# spice-usbm.net
KiCad netlist of a schematic drawn in EAGLE
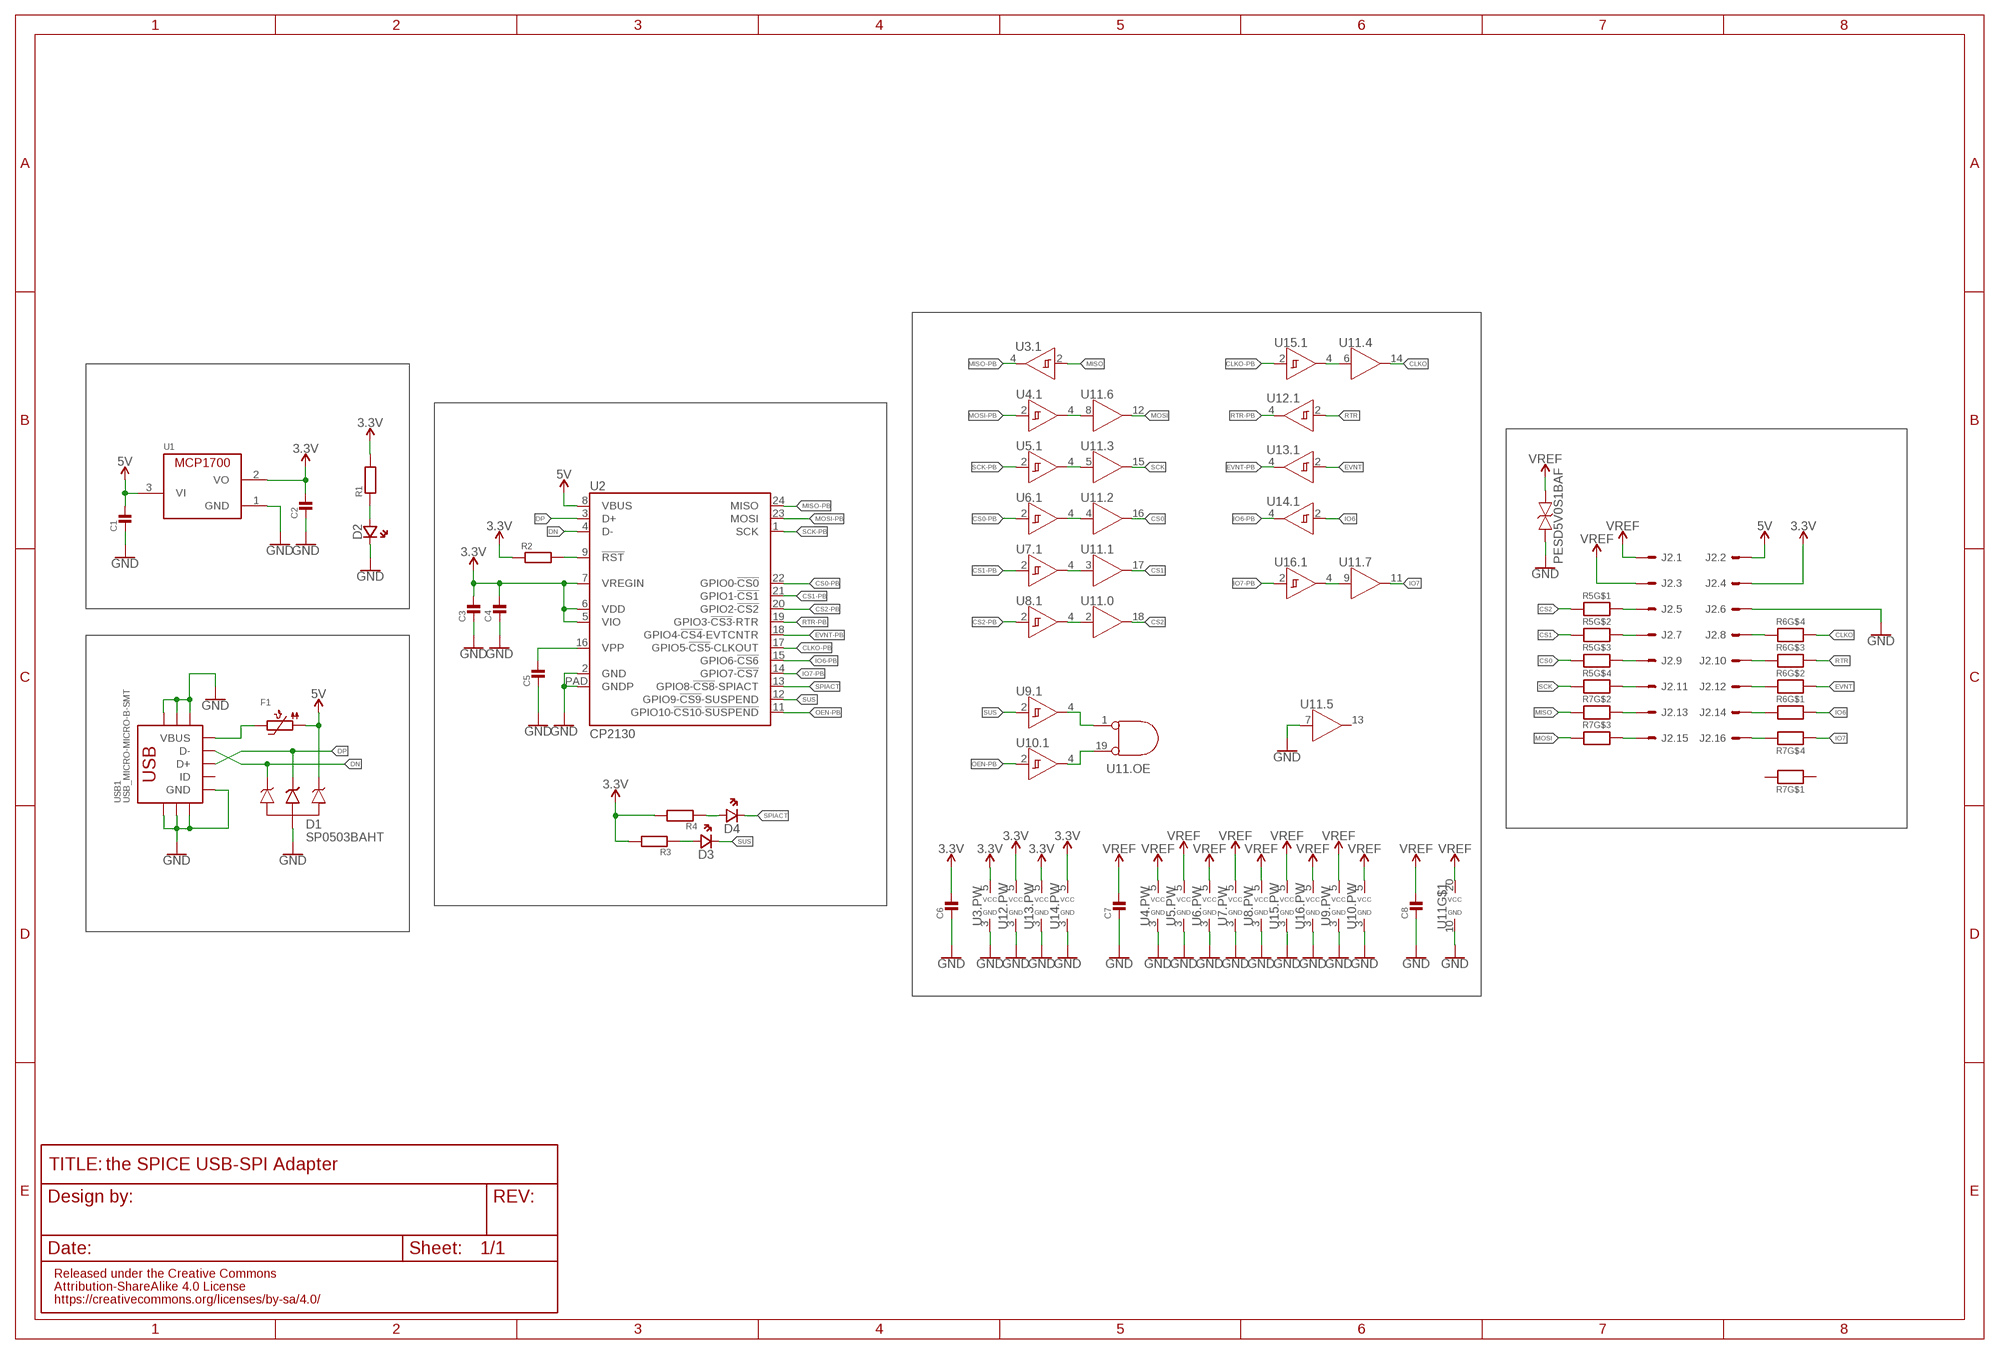
[diagram p0: schematic, sheet 1]

(export (version "E")
  (design (tool "Eeschema 10.0.6"))
  (components
    (comp (ref "C1")
      (value "MLCC0603")
      (footprint "eagle-import:0603_WAVE")
      (libsource (lib "eagle-import") (part "MLCC0603"))
    )
    (comp (ref "C2")
      (value "MLCC0603")
      (footprint "eagle-import:0603_WAVE")
      (libsource (lib "eagle-import") (part "MLCC0603"))
    )
    (comp (ref "C3")
      (value "MLCC0603")
      (footprint "eagle-import:0603_WAVE")
      (libsource (lib "eagle-import") (part "MLCC0603"))
    )
    (comp (ref "C4")
      (value "MLCC0603")
      (footprint "eagle-import:0603_WAVE")
      (libsource (lib "eagle-import") (part "MLCC0603"))
    )
    (comp (ref "C5")
      (value "MLCC0603")
      (footprint "eagle-import:0603_WAVE")
      (libsource (lib "eagle-import") (part "MLCC0603"))
    )
    (comp (ref "C6")
      (value "MLCC0603")
      (footprint "eagle-import:0603_WAVE")
      (libsource (lib "eagle-import") (part "MLCC0603"))
    )
    (comp (ref "C7")
      (value "MLCC0603")
      (footprint "eagle-import:0603_WAVE")
      (libsource (lib "eagle-import") (part "MLCC0603"))
    )
    (comp (ref "C8")
      (value "MLCC0603")
      (footprint "eagle-import:0603_WAVE")
      (libsource (lib "eagle-import") (part "MLCC0603"))
    )
    (comp (ref "D1")
      (value "SP0503BAHT")
      (footprint "eagle-import:SOT143")
      (libsource (lib "eagle-import") (part "SP0503BAHT"))
    )
    (comp (ref "D2")
      (value "LED0603")
      (footprint "eagle-import:CHIPLED_0603")
      (libsource (lib "eagle-import") (part "LED0603"))
    )
    (comp (ref "D3")
      (value "LED0603")
      (footprint "eagle-import:CHIPLED_0603")
      (libsource (lib "eagle-import") (part "LED0603"))
    )
    (comp (ref "D4")
      (value "LED0603")
      (footprint "eagle-import:CHIPLED_0603")
      (libsource (lib "eagle-import") (part "LED0603"))
    )
    (comp (ref "D5")
      (value "PESD5V0S1BAF")
      (footprint "eagle-import:SOD323")
      (libsource (lib "eagle-import") (part "PESD5V0S1BAF"))
    )
    (comp (ref "F1")
      (value "PTC1210")
      (footprint "eagle-import:PTC1210")
      (libsource (lib "eagle-import") (part "PTC1210"))
    )
    (comp (ref "J2")
      (value "2X8")
      (footprint "eagle-import:2X8_2.54")
      (libsource (lib "eagle-import") (part "2X8"))
    )
    (comp (ref "R1")
      (value "RESISTOR0603")
      (footprint "eagle-import:0603_WAVE")
      (libsource (lib "eagle-import") (part "RESISTOR0603"))
    )
    (comp (ref "R2")
      (value "RESISTOR0603")
      (footprint "eagle-import:0603_WAVE")
      (libsource (lib "eagle-import") (part "RESISTOR0603"))
    )
    (comp (ref "R3")
      (value "RESISTOR0603")
      (footprint "eagle-import:0603_WAVE")
      (libsource (lib "eagle-import") (part "RESISTOR0603"))
    )
    (comp (ref "R4")
      (value "RESISTOR0603")
      (footprint "eagle-import:0603_WAVE")
      (libsource (lib "eagle-import") (part "RESISTOR0603"))
    )
    (comp (ref "R5")
      (value "RESISTOR_4PACK")
      (footprint "eagle-import:RESPACK_4X0603")
      (libsource (lib "eagle-import") (part "RESISTOR_4PACK"))
    )
    (comp (ref "R6")
      (value "RESISTOR_4PACK")
      (footprint "eagle-import:RESPACK_4X0603")
      (libsource (lib "eagle-import") (part "RESISTOR_4PACK"))
    )
    (comp (ref "R7")
      (value "RESISTOR_4PACK")
      (footprint "eagle-import:RESPACK_4X0603")
      (libsource (lib "eagle-import") (part "RESISTOR_4PACK"))
    )
    (comp (ref "U1")
      (value "MCP1700T-3302TT")
      (footprint "eagle-import:SOT-23")
      (libsource (lib "eagle-import") (part "MCP1700T-3302TT"))
    )
    (comp (ref "U2")
      (value "CP2130")
      (footprint "eagle-import:QFN24")
      (libsource (lib "eagle-import") (part "CP2130"))
    )
    (comp (ref "U3")
      (value "74LVC1G17")
      (footprint "eagle-import:SC70-5")
      (libsource (lib "eagle-import") (part "74LVC1G17"))
    )
    (comp (ref "U4")
      (value "74LVC1G17")
      (footprint "eagle-import:SC70-5")
      (libsource (lib "eagle-import") (part "74LVC1G17"))
    )
    (comp (ref "U5")
      (value "74LVC1G17")
      (footprint "eagle-import:SC70-5")
      (libsource (lib "eagle-import") (part "74LVC1G17"))
    )
    (comp (ref "U6")
      (value "74LVC1G17")
      (footprint "eagle-import:SC70-5")
      (libsource (lib "eagle-import") (part "74LVC1G17"))
    )
    (comp (ref "U7")
      (value "74LVC1G17")
      (footprint "eagle-import:SC70-5")
      (libsource (lib "eagle-import") (part "74LVC1G17"))
    )
    (comp (ref "U8")
      (value "74LVC1G17")
      (footprint "eagle-import:SC70-5")
      (libsource (lib "eagle-import") (part "74LVC1G17"))
    )
    (comp (ref "U9")
      (value "74LVC1G17")
      (footprint "eagle-import:SC70-5")
      (libsource (lib "eagle-import") (part "74LVC1G17"))
    )
    (comp (ref "U10")
      (value "74LVC1G17")
      (footprint "eagle-import:SC70-5")
      (libsource (lib "eagle-import") (part "74LVC1G17"))
    )
    (comp (ref "U11")
      (value "74HC541")
      (footprint "eagle-import:TSSOP20")
      (libsource (lib "eagle-import") (part "74HC541"))
    )
    (comp (ref "U12")
      (value "74LVC1G17")
      (footprint "eagle-import:SC70-5")
      (libsource (lib "eagle-import") (part "74LVC1G17"))
    )
    (comp (ref "U13")
      (value "74LVC1G17")
      (footprint "eagle-import:SC70-5")
      (libsource (lib "eagle-import") (part "74LVC1G17"))
    )
    (comp (ref "U14")
      (value "74LVC1G17")
      (footprint "eagle-import:SC70-5")
      (libsource (lib "eagle-import") (part "74LVC1G17"))
    )
    (comp (ref "U15")
      (value "74LVC1G17")
      (footprint "eagle-import:SC70-5")
      (libsource (lib "eagle-import") (part "74LVC1G17"))
    )
    (comp (ref "U16")
      (value "74LVC1G17")
      (footprint "eagle-import:SC70-5")
      (libsource (lib "eagle-import") (part "74LVC1G17"))
    )
    (comp (ref "USB1")
      (value "USB_MICRO-MICRO-B-SMT")
      (footprint "eagle-import:USB-MICRO-SMD")
      (libsource (lib "eagle-import") (part "USB_MICRO-MICRO-B-SMT"))
    )
  )
  (nets
    (net (code "1") (name "3.3V") (class "Default")
      (node (ref "C2") (pin "P$1") (pinfunction "P$1_P$1") (pintype "bidirectional"))
      (node (ref "C3") (pin "P$1") (pinfunction "P$1_P$1") (pintype "bidirectional"))
      (node (ref "C4") (pin "P$1") (pinfunction "P$1_P$1") (pintype "bidirectional"))
      (node (ref "C6") (pin "P$1") (pinfunction "P$1_P$1") (pintype "bidirectional"))
      (node (ref "J2") (pin "4") (pinfunction "S_4") (pintype "passive"))
      (node (ref "R1") (pin "P$2") (pinfunction "P$2_P$2") (pintype "bidirectional"))
      (node (ref "R2") (pin "P$1") (pinfunction "P$1_P$1") (pintype "bidirectional"))
      (node (ref "R3") (pin "P$2") (pinfunction "P$2_P$2") (pintype "bidirectional"))
      (node (ref "R4") (pin "P$2") (pinfunction "P$2_P$2") (pintype "bidirectional"))
      (node (ref "U1") (pin "2") (pinfunction "VO_2") (pintype "bidirectional"))
      (node (ref "U12") (pin "5") (pinfunction "VCC_5") (pintype "bidirectional"))
      (node (ref "U13") (pin "5") (pinfunction "VCC_5") (pintype "bidirectional"))
      (node (ref "U14") (pin "5") (pinfunction "VCC_5") (pintype "bidirectional"))
      (node (ref "U2") (pin "5") (pinfunction "VIO_5") (pintype "bidirectional"))
      (node (ref "U2") (pin "6") (pinfunction "VDD_6") (pintype "bidirectional"))
      (node (ref "U2") (pin "7") (pinfunction "VREGIN_7") (pintype "bidirectional"))
      (node (ref "U3") (pin "5") (pinfunction "VCC_5") (pintype "bidirectional"))
    )
    (net (code "2") (name "5V") (class "Default")
      (node (ref "C1") (pin "P$1") (pinfunction "P$1_P$1") (pintype "bidirectional"))
      (node (ref "D1") (pin "4") (pinfunction "4_4") (pintype "bidirectional"))
      (node (ref "F1") (pin "P$1") (pinfunction "1_P$1") (pintype "passive"))
      (node (ref "J2") (pin "2") (pinfunction "S_2") (pintype "passive"))
      (node (ref "U1") (pin "3") (pinfunction "VI_3") (pintype "bidirectional"))
      (node (ref "U2") (pin "8") (pinfunction "VBUS_8") (pintype "bidirectional"))
    )
    (net (code "3") (name "CLKO") (class "Default")
      (node (ref "R6") (pin "5") (pinfunction "2_5") (pintype "passive"))
      (node (ref "U11") (pin "14") (pinfunction "Y_14") (pintype "output"))
    )
    (net (code "4") (name "CLKO-PB") (class "Default")
      (node (ref "U15") (pin "2") (pinfunction "A_2") (pintype "input"))
      (node (ref "U2") (pin "17") (pinfunction "GPIO5-~{CS5}-CLKOUT_17") (pintype "bidirectional"))
    )
    (net (code "5") (name "CS0") (class "Default")
      (node (ref "R5") (pin "3") (pinfunction "1_3") (pintype "passive"))
      (node (ref "U11") (pin "16") (pinfunction "Y_16") (pintype "output"))
    )
    (net (code "6") (name "CS0-PB") (class "Default")
      (node (ref "U2") (pin "22") (pinfunction "GPIO0-~{CS0}_22") (pintype "bidirectional"))
      (node (ref "U6") (pin "2") (pinfunction "A_2") (pintype "input"))
    )
    (net (code "7") (name "CS1") (class "Default")
      (node (ref "R5") (pin "2") (pinfunction "1_2") (pintype "passive"))
      (node (ref "U11") (pin "17") (pinfunction "Y_17") (pintype "output"))
    )
    (net (code "8") (name "CS1-PB") (class "Default")
      (node (ref "U2") (pin "21") (pinfunction "GPIO1-~{CS1}_21") (pintype "bidirectional"))
      (node (ref "U7") (pin "2") (pinfunction "A_2") (pintype "input"))
    )
    (net (code "9") (name "CS2") (class "Default")
      (node (ref "R5") (pin "1") (pinfunction "1_1") (pintype "passive"))
      (node (ref "U11") (pin "18") (pinfunction "Y_18") (pintype "output"))
    )
    (net (code "10") (name "CS2-PB") (class "Default")
      (node (ref "U2") (pin "20") (pinfunction "GPIO2-~{CS2}_20") (pintype "bidirectional"))
      (node (ref "U8") (pin "2") (pinfunction "A_2") (pintype "input"))
    )
    (net (code "11") (name "DN") (class "Default")
      (node (ref "D1") (pin "2") (pinfunction "2_2") (pintype "bidirectional"))
      (node (ref "U2") (pin "4") (pinfunction "D-_4") (pintype "bidirectional"))
      (node (ref "USB1") (pin "D-") (pinfunction "D-_D-") (pintype "bidirectional"))
    )
    (net (code "12") (name "DP") (class "Default")
      (node (ref "D1") (pin "3") (pinfunction "3_3") (pintype "bidirectional"))
      (node (ref "U2") (pin "3") (pinfunction "D+_3") (pintype "bidirectional"))
      (node (ref "USB1") (pin "D+") (pinfunction "D+_D+") (pintype "bidirectional"))
    )
    (net (code "13") (name "EVNT") (class "Default")
      (node (ref "R6") (pin "7") (pinfunction "2_7") (pintype "passive"))
      (node (ref "U13") (pin "2") (pinfunction "A_2") (pintype "input"))
    )
    (net (code "14") (name "EVNT-PB") (class "Default")
      (node (ref "U13") (pin "4") (pinfunction "Y_4") (pintype "output"))
      (node (ref "U2") (pin "18") (pinfunction "GPIO4-~{CS4}-EVTCNTR_18") (pintype "bidirectional"))
    )
    (net (code "15") (name "GND") (class "Default")
      (node (ref "C1") (pin "P$2") (pinfunction "P$2_P$2") (pintype "bidirectional"))
      (node (ref "C2") (pin "P$2") (pinfunction "P$2_P$2") (pintype "bidirectional"))
      (node (ref "C3") (pin "P$2") (pinfunction "P$2_P$2") (pintype "bidirectional"))
      (node (ref "C4") (pin "P$2") (pinfunction "P$2_P$2") (pintype "bidirectional"))
      (node (ref "C5") (pin "P$2") (pinfunction "P$2_P$2") (pintype "bidirectional"))
      (node (ref "C6") (pin "P$2") (pinfunction "P$2_P$2") (pintype "bidirectional"))
      (node (ref "C7") (pin "P$2") (pinfunction "P$2_P$2") (pintype "bidirectional"))
      (node (ref "C8") (pin "P$2") (pinfunction "P$2_P$2") (pintype "bidirectional"))
      (node (ref "D1") (pin "1") (pinfunction "1_1") (pintype "bidirectional"))
      (node (ref "D2") (pin "C") (pinfunction "CA_C") (pintype "bidirectional"))
      (node (ref "D5") (pin "P$2") (pinfunction "P$2_P$2") (pintype "bidirectional"))
      (node (ref "J2") (pin "6") (pinfunction "S_6") (pintype "passive"))
      (node (ref "U1") (pin "1") (pinfunction "GND_1") (pintype "bidirectional"))
      (node (ref "U10") (pin "3") (pinfunction "GND_3") (pintype "bidirectional"))
      (node (ref "U11") (pin "10") (pinfunction "GND_10") (pintype "bidirectional"))
      (node (ref "U11") (pin "7") (pinfunction "A_7") (pintype "input"))
      (node (ref "U12") (pin "3") (pinfunction "GND_3") (pintype "bidirectional"))
      (node (ref "U13") (pin "3") (pinfunction "GND_3") (pintype "bidirectional"))
      (node (ref "U14") (pin "3") (pinfunction "GND_3") (pintype "bidirectional"))
      (node (ref "U15") (pin "3") (pinfunction "GND_3") (pintype "bidirectional"))
      (node (ref "U16") (pin "3") (pinfunction "GND_3") (pintype "bidirectional"))
      (node (ref "U2") (pin "2") (pinfunction "GND_2") (pintype "bidirectional"))
      (node (ref "U2") (pin "PAD") (pinfunction "GNDP_PAD") (pintype "bidirectional"))
      (node (ref "U3") (pin "3") (pinfunction "GND_3") (pintype "bidirectional"))
      (node (ref "U4") (pin "3") (pinfunction "GND_3") (pintype "bidirectional"))
      (node (ref "U5") (pin "3") (pinfunction "GND_3") (pintype "bidirectional"))
      (node (ref "U6") (pin "3") (pinfunction "GND_3") (pintype "bidirectional"))
      (node (ref "U7") (pin "3") (pinfunction "GND_3") (pintype "bidirectional"))
      (node (ref "U8") (pin "3") (pinfunction "GND_3") (pintype "bidirectional"))
      (node (ref "U9") (pin "3") (pinfunction "GND_3") (pintype "bidirectional"))
      (node (ref "USB1") (pin "GND") (pinfunction "GND_GND") (pintype "bidirectional"))
      (node (ref "USB1") (pin "SHIELD1") (pinfunction "SHIELD_SHIELD1") (pintype "bidirectional"))
      (node (ref "USB1") (pin "SHIELD2") (pinfunction "SHIELD_SHIELD2") (pintype "bidirectional"))
      (node (ref "USB1") (pin "SHIELD3") (pinfunction "SHIELD_SHIELD3") (pintype "bidirectional"))
      (node (ref "USB1") (pin "SHIELD4") (pinfunction "SHIELD_SHIELD4") (pintype "bidirectional"))
      (node (ref "USB1") (pin "SHIELD5") (pinfunction "SHIELD_SHIELD5") (pintype "bidirectional"))
      (node (ref "USB1") (pin "SHIELD6") (pinfunction "SHIELD_SHIELD6") (pintype "bidirectional"))
    )
    (net (code "16") (name "IO6") (class "Default")
      (node (ref "R6") (pin "8") (pinfunction "2_8") (pintype "passive"))
      (node (ref "U14") (pin "2") (pinfunction "A_2") (pintype "input"))
    )
    (net (code "17") (name "IO6-PB") (class "Default")
      (node (ref "U14") (pin "4") (pinfunction "Y_4") (pintype "output"))
      (node (ref "U2") (pin "15") (pinfunction "GPIO6-~{CS6}_15") (pintype "bidirectional"))
    )
    (net (code "18") (name "IO7") (class "Default")
      (node (ref "R7") (pin "4") (pinfunction "1_4") (pintype "passive"))
      (node (ref "U11") (pin "11") (pinfunction "Y_11") (pintype "output"))
    )
    (net (code "19") (name "IO7-PB") (class "Default")
      (node (ref "U16") (pin "2") (pinfunction "A_2") (pintype "input"))
      (node (ref "U2") (pin "14") (pinfunction "GPIO7-~{CS7}_14") (pintype "bidirectional"))
    )
    (net (code "20") (name "MISO") (class "Default")
      (node (ref "R7") (pin "2") (pinfunction "1_2") (pintype "passive"))
      (node (ref "U3") (pin "2") (pinfunction "A_2") (pintype "input"))
    )
    (net (code "21") (name "MISO-PB") (class "Default")
      (node (ref "U2") (pin "24") (pinfunction "MISO_24") (pintype "bidirectional"))
      (node (ref "U3") (pin "4") (pinfunction "Y_4") (pintype "output"))
    )
    (net (code "22") (name "MOSI") (class "Default")
      (node (ref "R7") (pin "3") (pinfunction "1_3") (pintype "passive"))
      (node (ref "U11") (pin "12") (pinfunction "Y_12") (pintype "output"))
    )
    (net (code "23") (name "MOSI-PB") (class "Default")
      (node (ref "U2") (pin "23") (pinfunction "MOSI_23") (pintype "bidirectional"))
      (node (ref "U4") (pin "2") (pinfunction "A_2") (pintype "input"))
    )
    (net (code "24") (name "Net-(D2-AN)") (class "Default")
      (node (ref "D2") (pin "A") (pinfunction "AN_A") (pintype "bidirectional"))
      (node (ref "R1") (pin "P$1") (pinfunction "P$1_P$1") (pintype "bidirectional"))
    )
    (net (code "25") (name "Net-(D3-AN)") (class "Default")
      (node (ref "D3") (pin "A") (pinfunction "AN_A") (pintype "bidirectional"))
      (node (ref "R3") (pin "P$1") (pinfunction "P$1_P$1") (pintype "bidirectional"))
    )
    (net (code "26") (name "Net-(D4-AN)") (class "Default")
      (node (ref "D4") (pin "A") (pinfunction "AN_A") (pintype "bidirectional"))
      (node (ref "R4") (pin "P$1") (pinfunction "P$1_P$1") (pintype "bidirectional"))
    )
    (net (code "27") (name "Net-(F1-2)") (class "Default")
      (node (ref "F1") (pin "P$2") (pinfunction "2_P$2") (pintype "passive"))
      (node (ref "USB1") (pin "VBUS") (pinfunction "VBUS_VBUS") (pintype "bidirectional"))
    )
    (net (code "28") (name "Net-(J2B-S)") (class "Default")
      (node (ref "J2") (pin "10") (pinfunction "S_10") (pintype "passive"))
      (node (ref "R6") (pin "3") (pinfunction "1_3") (pintype "passive"))
    )
    (net (code "29") (name "Net-(J2C-S)") (class "Default")
      (node (ref "J2") (pin "11") (pinfunction "S_11") (pintype "passive"))
      (node (ref "R5") (pin "5") (pinfunction "2_5") (pintype "passive"))
    )
    (net (code "30") (name "Net-(J2D-S)") (class "Default")
      (node (ref "J2") (pin "12") (pinfunction "S_12") (pintype "passive"))
      (node (ref "R6") (pin "2") (pinfunction "1_2") (pintype "passive"))
    )
    (net (code "31") (name "Net-(J2E-S)") (class "Default")
      (node (ref "J2") (pin "13") (pinfunction "S_13") (pintype "passive"))
      (node (ref "R7") (pin "7") (pinfunction "2_7") (pintype "passive"))
    )
    (net (code "32") (name "Net-(J2F-S)") (class "Default")
      (node (ref "J2") (pin "14") (pinfunction "S_14") (pintype "passive"))
      (node (ref "R6") (pin "1") (pinfunction "1_1") (pintype "passive"))
    )
    (net (code "33") (name "Net-(J2G-S)") (class "Default")
      (node (ref "J2") (pin "15") (pinfunction "S_15") (pintype "passive"))
      (node (ref "R7") (pin "6") (pinfunction "2_6") (pintype "passive"))
    )
    (net (code "34") (name "Net-(J2H-S)") (class "Default")
      (node (ref "J2") (pin "16") (pinfunction "S_16") (pintype "passive"))
      (node (ref "R7") (pin "5") (pinfunction "2_5") (pintype "passive"))
    )
    (net (code "35") (name "Net-(J2L-S)") (class "Default")
      (node (ref "J2") (pin "5") (pinfunction "S_5") (pintype "passive"))
      (node (ref "R5") (pin "8") (pinfunction "2_8") (pintype "passive"))
    )
    (net (code "36") (name "Net-(J2N-S)") (class "Default")
      (node (ref "J2") (pin "7") (pinfunction "S_7") (pintype "passive"))
      (node (ref "R5") (pin "7") (pinfunction "2_7") (pintype "passive"))
    )
    (net (code "37") (name "Net-(J2O-S)") (class "Default")
      (node (ref "J2") (pin "8") (pinfunction "S_8") (pintype "passive"))
      (node (ref "R6") (pin "4") (pinfunction "1_4") (pintype "passive"))
    )
    (net (code "38") (name "Net-(J2P-S)") (class "Default")
      (node (ref "J2") (pin "9") (pinfunction "S_9") (pintype "passive"))
      (node (ref "R5") (pin "6") (pinfunction "2_6") (pintype "passive"))
    )
    (net (code "39") (name "Net-(U2-VPP)") (class "Default")
      (node (ref "C5") (pin "P$1") (pinfunction "P$1_P$1") (pintype "bidirectional"))
      (node (ref "U2") (pin "16") (pinfunction "VPP_16") (pintype "bidirectional"))
    )
    (net (code "40") (name "Net-(U2-~{RST})") (class "Default")
      (node (ref "R2") (pin "P$2") (pinfunction "P$2_P$2") (pintype "bidirectional"))
      (node (ref "U2") (pin "9") (pinfunction "~{RST}_9") (pintype "bidirectional"))
    )
    (net (code "41") (name "Net-(U10A-Y)") (class "Default")
      (node (ref "U10") (pin "4") (pinfunction "Y_4") (pintype "output"))
      (node (ref "U11") (pin "19") (pinfunction "B_19") (pintype "input"))
    )
    (net (code "42") (name "Net-(U11A-A)") (class "Default")
      (node (ref "U11") (pin "2") (pinfunction "A_2") (pintype "input"))
      (node (ref "U8") (pin "4") (pinfunction "Y_4") (pintype "output"))
    )
    (net (code "43") (name "Net-(U11B-A)") (class "Default")
      (node (ref "U11") (pin "3") (pinfunction "A_3") (pintype "input"))
      (node (ref "U7") (pin "4") (pinfunction "Y_4") (pintype "output"))
    )
    (net (code "44") (name "Net-(U11C-A)") (class "Default")
      (node (ref "U11") (pin "4") (pinfunction "A_4") (pintype "input"))
      (node (ref "U6") (pin "4") (pinfunction "Y_4") (pintype "output"))
    )
    (net (code "45") (name "Net-(U11D-A)") (class "Default")
      (node (ref "U11") (pin "5") (pinfunction "A_5") (pintype "input"))
      (node (ref "U5") (pin "4") (pinfunction "Y_4") (pintype "output"))
    )
    (net (code "46") (name "Net-(U11E-A)") (class "Default")
      (node (ref "U11") (pin "6") (pinfunction "A_6") (pintype "input"))
      (node (ref "U15") (pin "4") (pinfunction "Y_4") (pintype "output"))
    )
    (net (code "47") (name "Net-(U11G-A)") (class "Default")
      (node (ref "U11") (pin "8") (pinfunction "A_8") (pintype "input"))
      (node (ref "U4") (pin "4") (pinfunction "Y_4") (pintype "output"))
    )
    (net (code "48") (name "Net-(U11H-A)") (class "Default")
      (node (ref "U11") (pin "9") (pinfunction "A_9") (pintype "input"))
      (node (ref "U16") (pin "4") (pinfunction "Y_4") (pintype "output"))
    )
    (net (code "49") (name "Net-(U11I-A)") (class "Default")
      (node (ref "U11") (pin "1") (pinfunction "A_1") (pintype "input"))
      (node (ref "U9") (pin "4") (pinfunction "Y_4") (pintype "output"))
    )
    (net (code "50") (name "OEN-PB") (class "Default")
      (node (ref "U10") (pin "2") (pinfunction "A_2") (pintype "input"))
      (node (ref "U2") (pin "11") (pinfunction "GPIO10-~{CS10}-~{SUSPEND}_11") (pintype "bidirectional"))
    )
    (net (code "51") (name "RTR") (class "Default")
      (node (ref "R6") (pin "6") (pinfunction "2_6") (pintype "passive"))
      (node (ref "U12") (pin "2") (pinfunction "A_2") (pintype "input"))
    )
    (net (code "52") (name "RTR-PB") (class "Default")
      (node (ref "U12") (pin "4") (pinfunction "Y_4") (pintype "output"))
      (node (ref "U2") (pin "19") (pinfunction "GPIO3-~{CS3}-RTR_19") (pintype "bidirectional"))
    )
    (net (code "53") (name "SCK") (class "Default")
      (node (ref "R5") (pin "4") (pinfunction "1_4") (pintype "passive"))
      (node (ref "U11") (pin "15") (pinfunction "Y_15") (pintype "output"))
    )
    (net (code "54") (name "SCK-PB") (class "Default")
      (node (ref "U2") (pin "1") (pinfunction "SCK_1") (pintype "bidirectional"))
      (node (ref "U5") (pin "2") (pinfunction "A_2") (pintype "input"))
    )
    (net (code "55") (name "SPIACT") (class "Default")
      (node (ref "D4") (pin "C") (pinfunction "CA_C") (pintype "bidirectional"))
      (node (ref "U2") (pin "13") (pinfunction "GPIO8-~{CS8}-SPIACT_13") (pintype "bidirectional"))
    )
    (net (code "56") (name "SUS") (class "Default")
      (node (ref "D3") (pin "C") (pinfunction "CA_C") (pintype "bidirectional"))
      (node (ref "U2") (pin "12") (pinfunction "GPIO9-~{CS9}-SUSPEND_12") (pintype "bidirectional"))
      (node (ref "U9") (pin "2") (pinfunction "A_2") (pintype "input"))
    )
    (net (code "57") (name "VREF") (class "Default")
      (node (ref "C7") (pin "P$1") (pinfunction "P$1_P$1") (pintype "bidirectional"))
      (node (ref "C8") (pin "P$1") (pinfunction "P$1_P$1") (pintype "bidirectional"))
      (node (ref "D5") (pin "P$1") (pinfunction "P$1_P$1") (pintype "bidirectional"))
      (node (ref "J2") (pin "1") (pinfunction "S_1") (pintype "passive"))
      (node (ref "J2") (pin "3") (pinfunction "S_3") (pintype "passive"))
      (node (ref "U10") (pin "5") (pinfunction "VCC_5") (pintype "bidirectional"))
      (node (ref "U11") (pin "20") (pinfunction "VCC_20") (pintype "bidirectional"))
      (node (ref "U15") (pin "5") (pinfunction "VCC_5") (pintype "bidirectional"))
      (node (ref "U16") (pin "5") (pinfunction "VCC_5") (pintype "bidirectional"))
      (node (ref "U4") (pin "5") (pinfunction "VCC_5") (pintype "bidirectional"))
      (node (ref "U5") (pin "5") (pinfunction "VCC_5") (pintype "bidirectional"))
      (node (ref "U6") (pin "5") (pinfunction "VCC_5") (pintype "bidirectional"))
      (node (ref "U7") (pin "5") (pinfunction "VCC_5") (pintype "bidirectional"))
      (node (ref "U8") (pin "5") (pinfunction "VCC_5") (pintype "bidirectional"))
      (node (ref "U9") (pin "5") (pinfunction "VCC_5") (pintype "bidirectional"))
    )
    (net (code "58") (name "unconnected-(R7-Pad1)") (class "Default")
      (node (ref "R7") (pin "1") (pinfunction "1_1") (pintype "passive"))
    )
    (net (code "59") (name "unconnected-(R7A-2-Pad8)") (class "Default")
      (node (ref "R7") (pin "8") (pinfunction "2_8") (pintype "passive"))
    )
    (net (code "60") (name "unconnected-(U11F-Y-Pad13)") (class "Default")
      (node (ref "U11") (pin "13") (pinfunction "Y_13") (pintype "output"))
    )
    (net (code "61") (name "unconnected-(USB1-PadID)") (class "Default")
      (node (ref "USB1") (pin "ID") (pinfunction "ID_ID") (pintype "bidirectional"))
    )
  )
)
